# Amplifier.net
KiCad netlist of a schematic drawn in Altium Designer
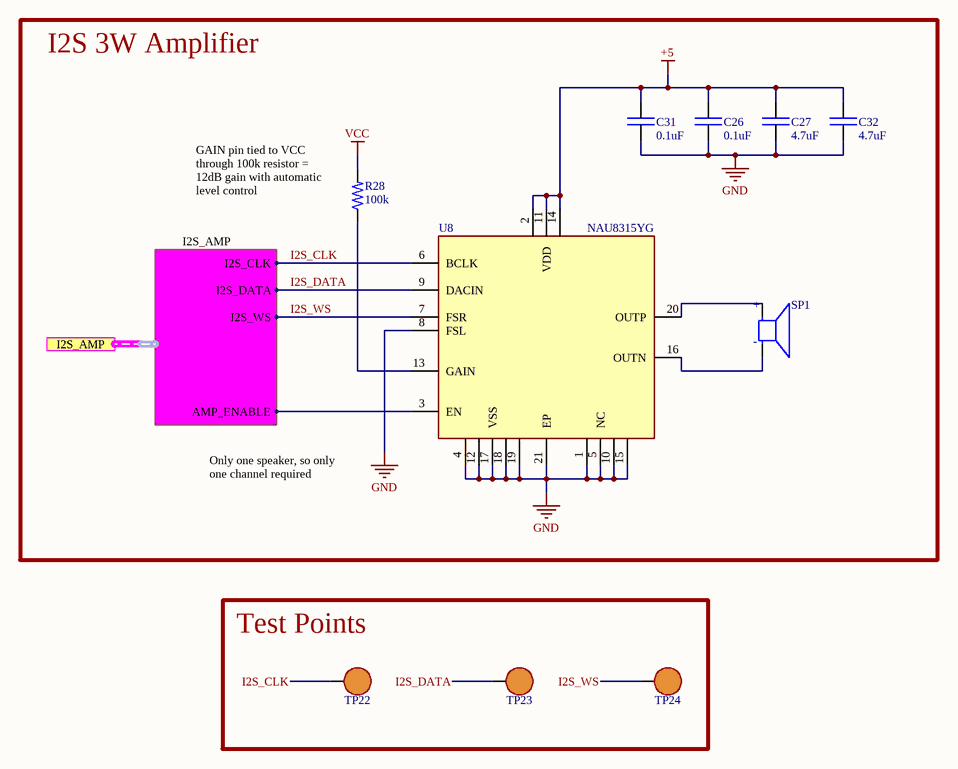
[diagram p0: Amplifier.SchDoc]

(export (version "E")
  (design (tool "Eeschema 10.0.6"))
  (components
    (comp (ref "C26")
      (value "0.1uF")
      (footprint "Beethoven-clock:0402C")
      (description "Capacitor")
      (fields (field (name "MFR") "Murata Electronics") (field (name "Comment") "CAP"))
      (libsource (lib "Beethoven-clock") (part "CAP"))
    )
    (comp (ref "C27")
      (value "4.7uF")
      (footprint "Beethoven-clock:0402C")
      (description "Capacitor")
      (fields (field (name "MFR") "Murata Electronics") (field (name "Comment") "CAP"))
      (libsource (lib "Beethoven-clock") (part "CAP"))
    )
    (comp (ref "C31")
      (value "0.1uF")
      (footprint "Beethoven-clock:0402C")
      (description "Capacitor")
      (fields (field (name "MFR") "Murata Electronics") (field (name "Comment") "CAP"))
      (libsource (lib "Beethoven-clock") (part "CAP"))
    )
    (comp (ref "C32")
      (value "4.7uF")
      (footprint "Beethoven-clock:0402C")
      (description "Capacitor")
      (fields (field (name "MFR") "Murata Electronics") (field (name "Comment") "CAP"))
      (libsource (lib "Beethoven-clock") (part "CAP"))
    )
    (comp (ref "R28")
      (value "100k")
      (footprint "Beethoven-clock:0402R")
      (description "Resistor")
      (fields (field (name "MFR") "YAGEO") (field (name "TOLERANCE") "+/- 5%"))
      (libsource (lib "Beethoven-clock") (part "RES"))
    )
    (comp (ref "SP1")
      (value "AS07104PO-LW152-R")
      (footprint "Beethoven-clock:26AWG_AS04004PO-2-LW152-R_SideMount")
      (description "SPEAKER 4OHM 3W TOP PORT 86DB")
      (fields (field (name "MFR") "PUI Audio, Inc."))
      (libsource (lib "Beethoven-clock") (part "SPEAKER 4OHM 3W"))
    )
    (comp (ref "TP22")
      (value "RCWCTE")
      (footprint "Beethoven-clock:RCWCTE")
      (description "Test Point, Surface Mount")
      (fields (field (name "MFR") "KOA Speer Electronics, Inc."))
      (libsource (lib "Beethoven-clock") (part "TEST POINT"))
    )
    (comp (ref "TP23")
      (value "RCWCTE")
      (footprint "Beethoven-clock:RCWCTE")
      (description "Test Point, Surface Mount")
      (fields (field (name "MFR") "KOA Speer Electronics, Inc."))
      (libsource (lib "Beethoven-clock") (part "TEST POINT"))
    )
    (comp (ref "TP24")
      (value "RCWCTE")
      (footprint "Beethoven-clock:RCWCTE")
      (description "Test Point, Surface Mount")
      (fields (field (name "MFR") "KOA Speer Electronics, Inc."))
      (libsource (lib "Beethoven-clock") (part "TEST POINT"))
    )
    (comp (ref "U8")
      (value "NAU8315YG")
      (footprint "Beethoven-clock:20-WFQFN-EP")
      (description "I2S MONO 3.2W CLASS-D AMPLIFIER")
      (fields (field (name "MFR") "Nuvoton"))
      (libsource (lib "Beethoven-clock") (part "I2S 3W AMP"))
    )
  )
  (nets
    (net (code "2") (name "+5") (class "Default")
      (node (ref "C26") (pin "2") (pinfunction "2_2") (pintype "passive"))
      (node (ref "C27") (pin "2") (pinfunction "2_2") (pintype "passive"))
      (node (ref "C31") (pin "2") (pinfunction "2_2") (pintype "passive"))
      (node (ref "C32") (pin "2") (pinfunction "2_2") (pintype "passive"))
      (node (ref "U8") (pin "11") (pinfunction "VDD_11") (pintype "passive"))
      (node (ref "U8") (pin "14") (pinfunction "VDD_14") (pintype "passive"))
      (node (ref "U8") (pin "2") (pinfunction "VDD_2") (pintype "passive"))
    )
    (net (code "3") (name "/AMP_ENABLE") (class "Default")
      (node (ref "U8") (pin "3") (pinfunction "EN_3") (pintype "passive"))
    )
    (net (code "4") (name "/I2S_CLK") (class "Default")
      (node (ref "TP22") (pin "1") (pinfunction "0_1") (pintype "passive"))
      (node (ref "U8") (pin "6") (pinfunction "BCLK_6") (pintype "passive"))
    )
    (net (code "5") (name "/I2S_DATA") (class "Default")
      (node (ref "TP23") (pin "1") (pinfunction "0_1") (pintype "passive"))
      (node (ref "U8") (pin "9") (pinfunction "DACIN_9") (pintype "passive"))
    )
    (net (code "6") (name "/I2S_WS") (class "Default")
      (node (ref "TP24") (pin "1") (pinfunction "0_1") (pintype "passive"))
      (node (ref "U8") (pin "7") (pinfunction "FSR_7") (pintype "passive"))
    )
    (net (code "8") (name "GND") (class "Default")
      (node (ref "C26") (pin "1") (pinfunction "1_1") (pintype "passive"))
      (node (ref "C27") (pin "1") (pinfunction "1_1") (pintype "passive"))
      (node (ref "C31") (pin "1") (pinfunction "1_1") (pintype "passive"))
      (node (ref "C32") (pin "1") (pinfunction "1_1") (pintype "passive"))
      (node (ref "U8") (pin "1") (pinfunction "NC_1") (pintype "passive"))
      (node (ref "U8") (pin "10") (pinfunction "NC_10") (pintype "passive"))
      (node (ref "U8") (pin "12") (pinfunction "VSS_12") (pintype "passive"))
      (node (ref "U8") (pin "15") (pinfunction "NC_15") (pintype "passive"))
      (node (ref "U8") (pin "17") (pinfunction "VSS_17") (pintype "passive"))
      (node (ref "U8") (pin "18") (pinfunction "VSS_18") (pintype "passive"))
      (node (ref "U8") (pin "19") (pinfunction "VSS_19") (pintype "passive"))
      (node (ref "U8") (pin "21") (pinfunction "EP_21") (pintype "passive"))
      (node (ref "U8") (pin "4") (pinfunction "VSS_4") (pintype "passive"))
      (node (ref "U8") (pin "5") (pinfunction "NC_5") (pintype "passive"))
      (node (ref "U8") (pin "8") (pinfunction "FSL_8") (pintype "passive"))
    )
    (net (code "9") (name "Net-(U8-GAIN)") (class "Default")
      (node (ref "R28") (pin "1") (pinfunction "1_1") (pintype "passive"))
      (node (ref "U8") (pin "13") (pinfunction "GAIN_13") (pintype "passive"))
    )
    (net (code "10") (name "Net-(U8-OUTN)") (class "Default")
      (node (ref "SP1") (pin "N") (pinfunction "N_N") (pintype "passive"))
      (node (ref "U8") (pin "16") (pinfunction "OUTN_16") (pintype "passive"))
    )
    (net (code "11") (name "Net-(U8-OUTP)") (class "Default")
      (node (ref "SP1") (pin "P") (pinfunction "P_P") (pintype "passive"))
      (node (ref "U8") (pin "20") (pinfunction "OUTP_20") (pintype "passive"))
    )
    (net (code "12") (name "VCC") (class "Default")
      (node (ref "R28") (pin "2") (pinfunction "2_2") (pintype "passive"))
    )
  )
)
